# E_KEYPAD__2_1.net
KiCad netlist of a schematic drawn in EAGLE
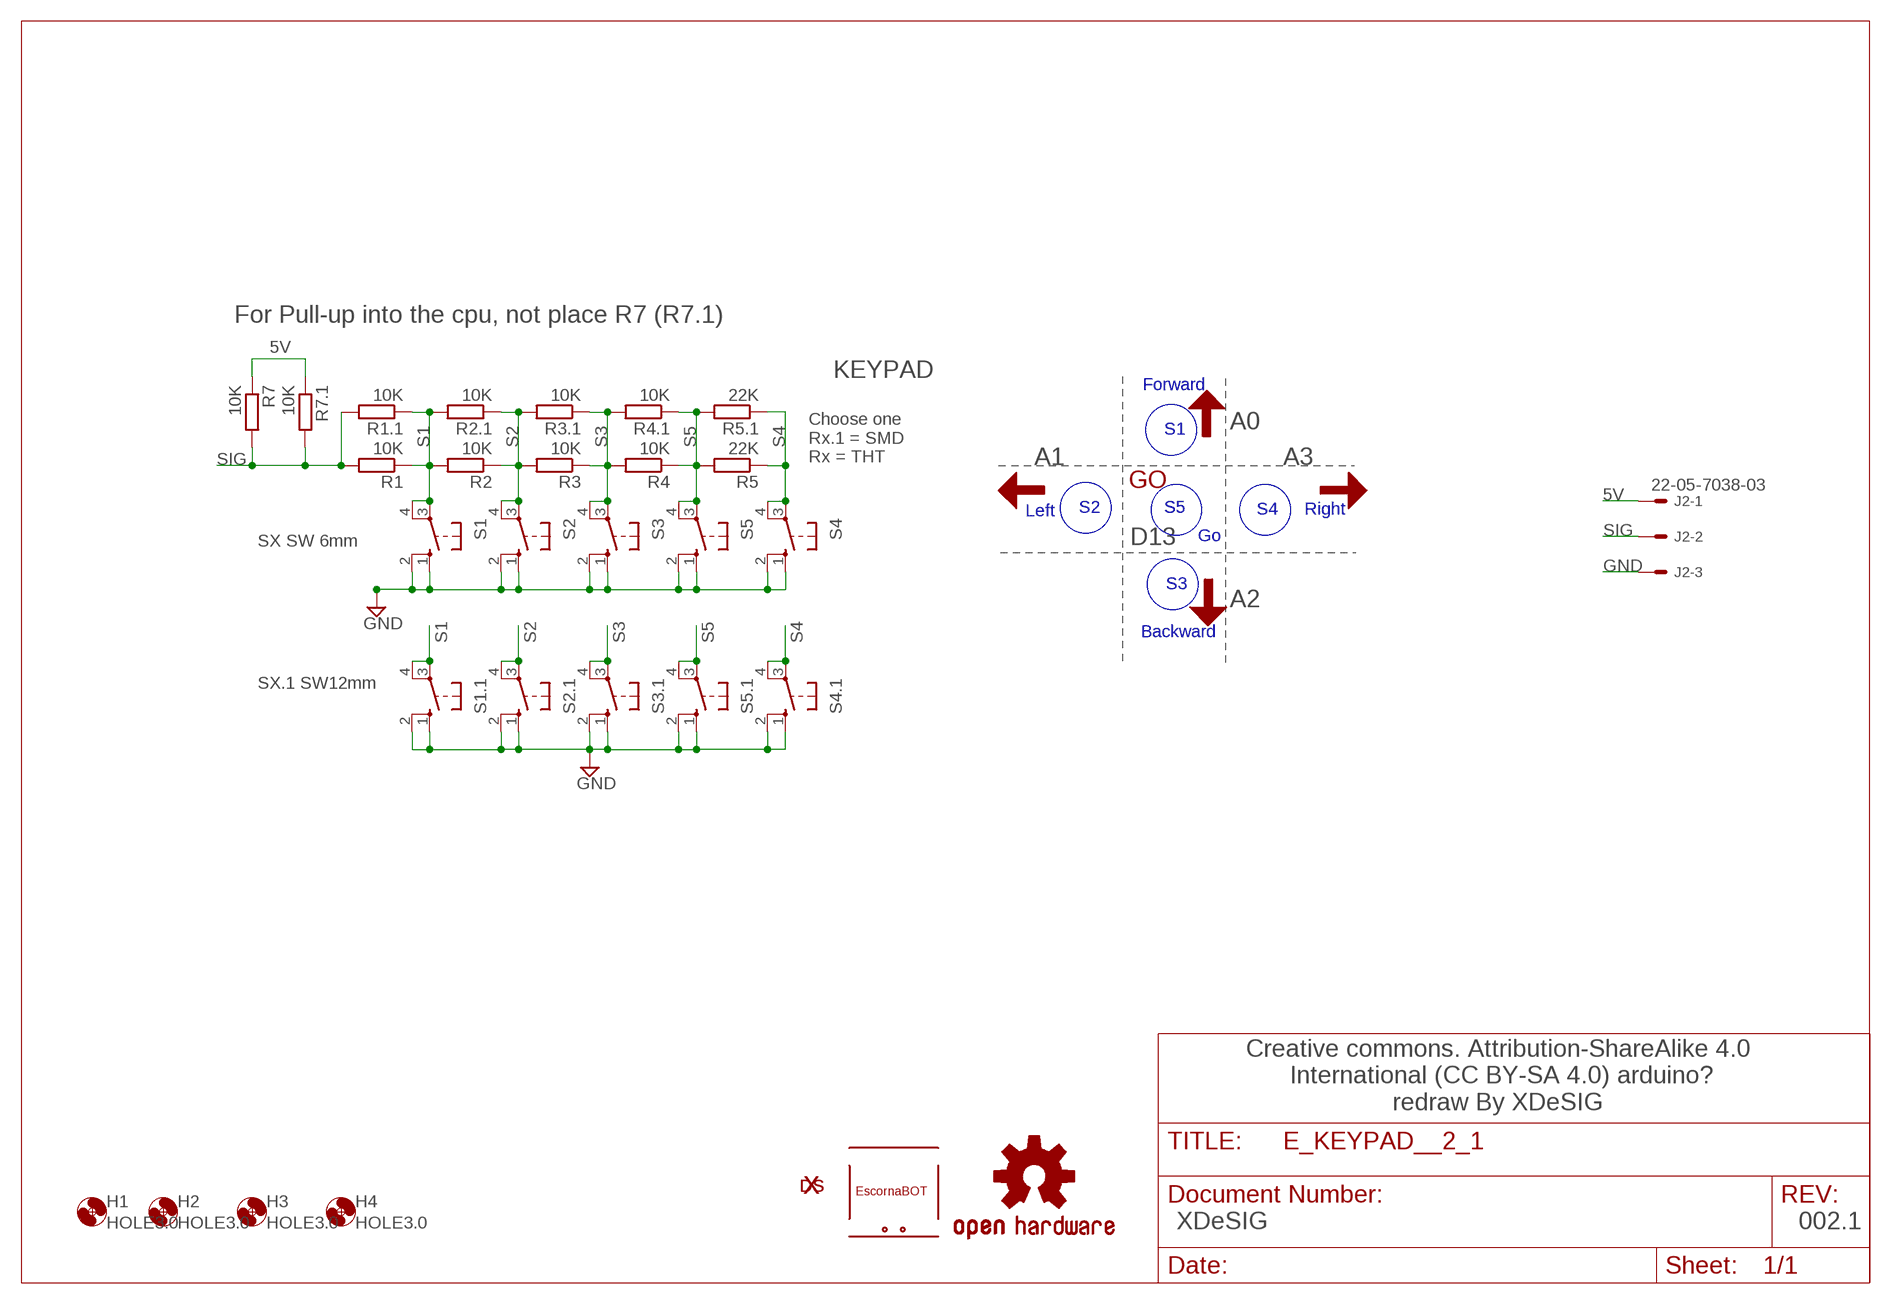
[diagram p0: schematic, sheet 1]

(export (version "E")
  (design (tool "Eeschema 10.0.6"))
  (components
    (comp (ref "H1")
      (value "HOLE3.0")
      (footprint "eagle-import:3,0")
      (libsource (lib "eagle-import") (part "MOUNT-HOLE3.0"))
    )
    (comp (ref "H2")
      (value "HOLE3.0")
      (footprint "eagle-import:3,0")
      (libsource (lib "eagle-import") (part "MOUNT-HOLE3.0"))
    )
    (comp (ref "H3")
      (value "HOLE3.0")
      (footprint "eagle-import:3,0")
      (libsource (lib "eagle-import") (part "MOUNT-HOLE3.0"))
    )
    (comp (ref "H4")
      (value "HOLE3.0")
      (footprint "eagle-import:3,0")
      (libsource (lib "eagle-import") (part "MOUNT-HOLE3.0"))
    )
    (comp (ref "J2")
      (value "22-05-7038-03")
      (footprint "eagle-import:7395-03")
      (libsource (lib "eagle-import") (part "22-?-0305-7038"))
    )
    (comp (ref "LOGO2")
      (value "OSHW-LOGOS")
      (footprint "eagle-import:OSHW-LOGO-S")
      (libsource (lib "eagle-import") (part "OSHW-LOGOS"))
    )
    (comp (ref "R1")
      (value "10K")
      (footprint "eagle-import:0204_7")
      (libsource (lib "eagle-import") (part "R-EU_0204/7"))
    )
    (comp (ref "R1.1")
      (value "10K")
      (footprint "eagle-import:R0603")
      (libsource (lib "eagle-import") (part "R-EU_R0603"))
    )
    (comp (ref "R2")
      (value "10K")
      (footprint "eagle-import:0204_7")
      (libsource (lib "eagle-import") (part "R-EU_0204/7"))
    )
    (comp (ref "R2.1")
      (value "10K")
      (footprint "eagle-import:R0603")
      (libsource (lib "eagle-import") (part "R-EU_R0603"))
    )
    (comp (ref "R3")
      (value "10K")
      (footprint "eagle-import:0204_7")
      (libsource (lib "eagle-import") (part "R-EU_0204/7"))
    )
    (comp (ref "R3.1")
      (value "10K")
      (footprint "eagle-import:R0603")
      (libsource (lib "eagle-import") (part "R-EU_R0603"))
    )
    (comp (ref "R4")
      (value "10K")
      (footprint "eagle-import:0204_7")
      (libsource (lib "eagle-import") (part "R-EU_0204/7"))
    )
    (comp (ref "R4.1")
      (value "10K")
      (footprint "eagle-import:R0603")
      (libsource (lib "eagle-import") (part "R-EU_R0603"))
    )
    (comp (ref "R5")
      (value "22K")
      (footprint "eagle-import:0204_7")
      (libsource (lib "eagle-import") (part "R-EU_0204/7"))
    )
    (comp (ref "R5.1")
      (value "22K")
      (footprint "eagle-import:R0603")
      (libsource (lib "eagle-import") (part "R-EU_R0603"))
    )
    (comp (ref "R7")
      (value "10K")
      (footprint "eagle-import:0204_7")
      (libsource (lib "eagle-import") (part "R-EU_0204/7"))
    )
    (comp (ref "R7.1")
      (value "10K")
      (footprint "eagle-import:R0603")
      (libsource (lib "eagle-import") (part "R-EU_R0603"))
    )
    (comp (ref "S1")
      (value "10-XX")
      (footprint "eagle-import:B3F-10XX")
      (fields (field (name "MPN") "B3F-1000"))
      (libsource (lib "eagle-import") (part "10-XX"))
    )
    (comp (ref "S1.1")
      (value "40-XX")
      (footprint "eagle-import:B3F-40XX")
      (fields (field (name "MF") "OMRON COMPONENTS USA") (field (name "MPN") "B3F-4000"))
      (libsource (lib "eagle-import") (part "40-XX"))
    )
    (comp (ref "S2")
      (value "10-XX")
      (footprint "eagle-import:B3F-10XX")
      (fields (field (name "MPN") "B3F-1000"))
      (libsource (lib "eagle-import") (part "10-XX"))
    )
    (comp (ref "S2.1")
      (value "40-XX")
      (footprint "eagle-import:B3F-40XX")
      (fields (field (name "MF") "OMRON COMPONENTS USA") (field (name "MPN") "B3F-4000"))
      (libsource (lib "eagle-import") (part "40-XX"))
    )
    (comp (ref "S3")
      (value "10-XX")
      (footprint "eagle-import:B3F-10XX")
      (fields (field (name "MPN") "B3F-1000"))
      (libsource (lib "eagle-import") (part "10-XX"))
    )
    (comp (ref "S3.1")
      (value "40-XX")
      (footprint "eagle-import:B3F-40XX")
      (fields (field (name "MF") "OMRON COMPONENTS USA") (field (name "MPN") "B3F-4000"))
      (libsource (lib "eagle-import") (part "40-XX"))
    )
    (comp (ref "S4")
      (value "10-XX")
      (footprint "eagle-import:B3F-10XX")
      (fields (field (name "MPN") "B3F-1000"))
      (libsource (lib "eagle-import") (part "10-XX"))
    )
    (comp (ref "S4.1")
      (value "40-XX")
      (footprint "eagle-import:B3F-40XX")
      (fields (field (name "MF") "OMRON COMPONENTS USA") (field (name "MPN") "B3F-4000"))
      (libsource (lib "eagle-import") (part "40-XX"))
    )
    (comp (ref "S5")
      (value "10-XX")
      (footprint "eagle-import:B3F-10XX")
      (fields (field (name "MPN") "B3F-1000"))
      (libsource (lib "eagle-import") (part "10-XX"))
    )
    (comp (ref "S5.1")
      (value "40-XX")
      (footprint "eagle-import:B3F-40XX")
      (fields (field (name "MF") "OMRON COMPONENTS USA") (field (name "MPN") "B3F-4000"))
      (libsource (lib "eagle-import") (part "40-XX"))
    )
    (comp (ref "U$1")
      (value "ESCORNABOT")
      (footprint "eagle-import:ESCORNA_PEQUE")
      (libsource (lib "eagle-import") (part "ESCORNABOT"))
    )
    (comp (ref "U$3")
      (value "FRECHA")
      (footprint "eagle-import:FRECHA")
      (libsource (lib "eagle-import") (part "FRECHA"))
    )
    (comp (ref "U$4")
      (value "FRECHA")
      (footprint "eagle-import:FRECHA")
      (libsource (lib "eagle-import") (part "FRECHA"))
    )
    (comp (ref "U$5")
      (value "GO")
      (footprint "eagle-import:VALE")
      (libsource (lib "eagle-import") (part "GO"))
    )
    (comp (ref "U$6")
      (value "FRECHA")
      (footprint "eagle-import:FRECHA")
      (libsource (lib "eagle-import") (part "FRECHA"))
    )
    (comp (ref "U$7")
      (value "XDESIG21")
      (footprint "eagle-import:XDESIG")
      (libsource (lib "eagle-import") (part "XDESIG21"))
    )
    (comp (ref "U$8")
      (value "XDESIG")
      (footprint "eagle-import:XDESIG_CU_2")
      (libsource (lib "eagle-import") (part "XDESIG"))
    )
    (comp (ref "U$11")
      (value "FRECHA")
      (footprint "eagle-import:FRECHA")
      (libsource (lib "eagle-import") (part "FRECHA"))
    )
  )
  (nets
    (net (code "1") (name "/5V") (class "Default")
      (node (ref "J2") (pin "1") (pinfunction "S_1") (pintype "passive"))
      (node (ref "R7") (pin "1") (pinfunction "1_1") (pintype "passive"))
      (node (ref "R7.1") (pin "1") (pinfunction "1_1") (pintype "passive"))
    )
    (net (code "2") (name "/S1") (class "Default")
      (node (ref "R1") (pin "1") (pinfunction "1_1") (pintype "passive"))
      (node (ref "R1.1") (pin "1") (pinfunction "1_1") (pintype "passive"))
      (node (ref "R2") (pin "2") (pinfunction "2_2") (pintype "passive"))
      (node (ref "R2.1") (pin "2") (pinfunction "2_2") (pintype "passive"))
      (node (ref "S1") (pin "3") (pinfunction "P_3") (pintype "passive"))
      (node (ref "S1") (pin "4") (pinfunction "P1_4") (pintype "passive"))
      (node (ref "S1.1") (pin "3") (pinfunction "P_3") (pintype "passive"))
      (node (ref "S1.1") (pin "4") (pinfunction "P1_4") (pintype "passive"))
    )
    (net (code "3") (name "/S2") (class "Default")
      (node (ref "R2") (pin "1") (pinfunction "1_1") (pintype "passive"))
      (node (ref "R2.1") (pin "1") (pinfunction "1_1") (pintype "passive"))
      (node (ref "R3") (pin "2") (pinfunction "2_2") (pintype "passive"))
      (node (ref "R3.1") (pin "2") (pinfunction "2_2") (pintype "passive"))
      (node (ref "S2") (pin "3") (pinfunction "P_3") (pintype "passive"))
      (node (ref "S2") (pin "4") (pinfunction "P1_4") (pintype "passive"))
      (node (ref "S2.1") (pin "3") (pinfunction "P_3") (pintype "passive"))
      (node (ref "S2.1") (pin "4") (pinfunction "P1_4") (pintype "passive"))
    )
    (net (code "4") (name "/S3") (class "Default")
      (node (ref "R3") (pin "1") (pinfunction "1_1") (pintype "passive"))
      (node (ref "R3.1") (pin "1") (pinfunction "1_1") (pintype "passive"))
      (node (ref "R4") (pin "2") (pinfunction "2_2") (pintype "passive"))
      (node (ref "R4.1") (pin "2") (pinfunction "2_2") (pintype "passive"))
      (node (ref "S3") (pin "3") (pinfunction "P_3") (pintype "passive"))
      (node (ref "S3") (pin "4") (pinfunction "P1_4") (pintype "passive"))
      (node (ref "S3.1") (pin "3") (pinfunction "P_3") (pintype "passive"))
      (node (ref "S3.1") (pin "4") (pinfunction "P1_4") (pintype "passive"))
    )
    (net (code "5") (name "/S4") (class "Default")
      (node (ref "R5") (pin "1") (pinfunction "1_1") (pintype "passive"))
      (node (ref "R5.1") (pin "1") (pinfunction "1_1") (pintype "passive"))
      (node (ref "S4") (pin "3") (pinfunction "P_3") (pintype "passive"))
      (node (ref "S4") (pin "4") (pinfunction "P1_4") (pintype "passive"))
      (node (ref "S4.1") (pin "3") (pinfunction "P_3") (pintype "passive"))
      (node (ref "S4.1") (pin "4") (pinfunction "P1_4") (pintype "passive"))
    )
    (net (code "6") (name "/S5") (class "Default")
      (node (ref "R4") (pin "1") (pinfunction "1_1") (pintype "passive"))
      (node (ref "R4.1") (pin "1") (pinfunction "1_1") (pintype "passive"))
      (node (ref "R5") (pin "2") (pinfunction "2_2") (pintype "passive"))
      (node (ref "R5.1") (pin "2") (pinfunction "2_2") (pintype "passive"))
      (node (ref "S5") (pin "3") (pinfunction "P_3") (pintype "passive"))
      (node (ref "S5") (pin "4") (pinfunction "P1_4") (pintype "passive"))
      (node (ref "S5.1") (pin "3") (pinfunction "P_3") (pintype "passive"))
      (node (ref "S5.1") (pin "4") (pinfunction "P1_4") (pintype "passive"))
    )
    (net (code "7") (name "/SIG") (class "Default")
      (node (ref "J2") (pin "2") (pinfunction "S_2") (pintype "passive"))
      (node (ref "R1") (pin "2") (pinfunction "2_2") (pintype "passive"))
      (node (ref "R1.1") (pin "2") (pinfunction "2_2") (pintype "passive"))
      (node (ref "R7") (pin "2") (pinfunction "2_2") (pintype "passive"))
      (node (ref "R7.1") (pin "2") (pinfunction "2_2") (pintype "passive"))
    )
    (net (code "8") (name "GND") (class "Default")
      (node (ref "J2") (pin "3") (pinfunction "S_3") (pintype "passive"))
      (node (ref "S1") (pin "1") (pinfunction "S_1") (pintype "passive"))
      (node (ref "S1") (pin "2") (pinfunction "S1_2") (pintype "passive"))
      (node (ref "S1.1") (pin "1") (pinfunction "S_1") (pintype "passive"))
      (node (ref "S1.1") (pin "2") (pinfunction "S1_2") (pintype "passive"))
      (node (ref "S2") (pin "1") (pinfunction "S_1") (pintype "passive"))
      (node (ref "S2") (pin "2") (pinfunction "S1_2") (pintype "passive"))
      (node (ref "S2.1") (pin "1") (pinfunction "S_1") (pintype "passive"))
      (node (ref "S2.1") (pin "2") (pinfunction "S1_2") (pintype "passive"))
      (node (ref "S3") (pin "1") (pinfunction "S_1") (pintype "passive"))
      (node (ref "S3") (pin "2") (pinfunction "S1_2") (pintype "passive"))
      (node (ref "S3.1") (pin "1") (pinfunction "S_1") (pintype "passive"))
      (node (ref "S3.1") (pin "2") (pinfunction "S1_2") (pintype "passive"))
      (node (ref "S4") (pin "1") (pinfunction "S_1") (pintype "passive"))
      (node (ref "S4") (pin "2") (pinfunction "S1_2") (pintype "passive"))
      (node (ref "S4.1") (pin "1") (pinfunction "S_1") (pintype "passive"))
      (node (ref "S4.1") (pin "2") (pinfunction "S1_2") (pintype "passive"))
      (node (ref "S5") (pin "1") (pinfunction "S_1") (pintype "passive"))
      (node (ref "S5") (pin "2") (pinfunction "S1_2") (pintype "passive"))
      (node (ref "S5.1") (pin "1") (pinfunction "S_1") (pintype "passive"))
      (node (ref "S5.1") (pin "2") (pinfunction "S1_2") (pintype "passive"))
    )
  )
)
